# MCU.net
KiCad netlist of a schematic drawn in Altium Designer
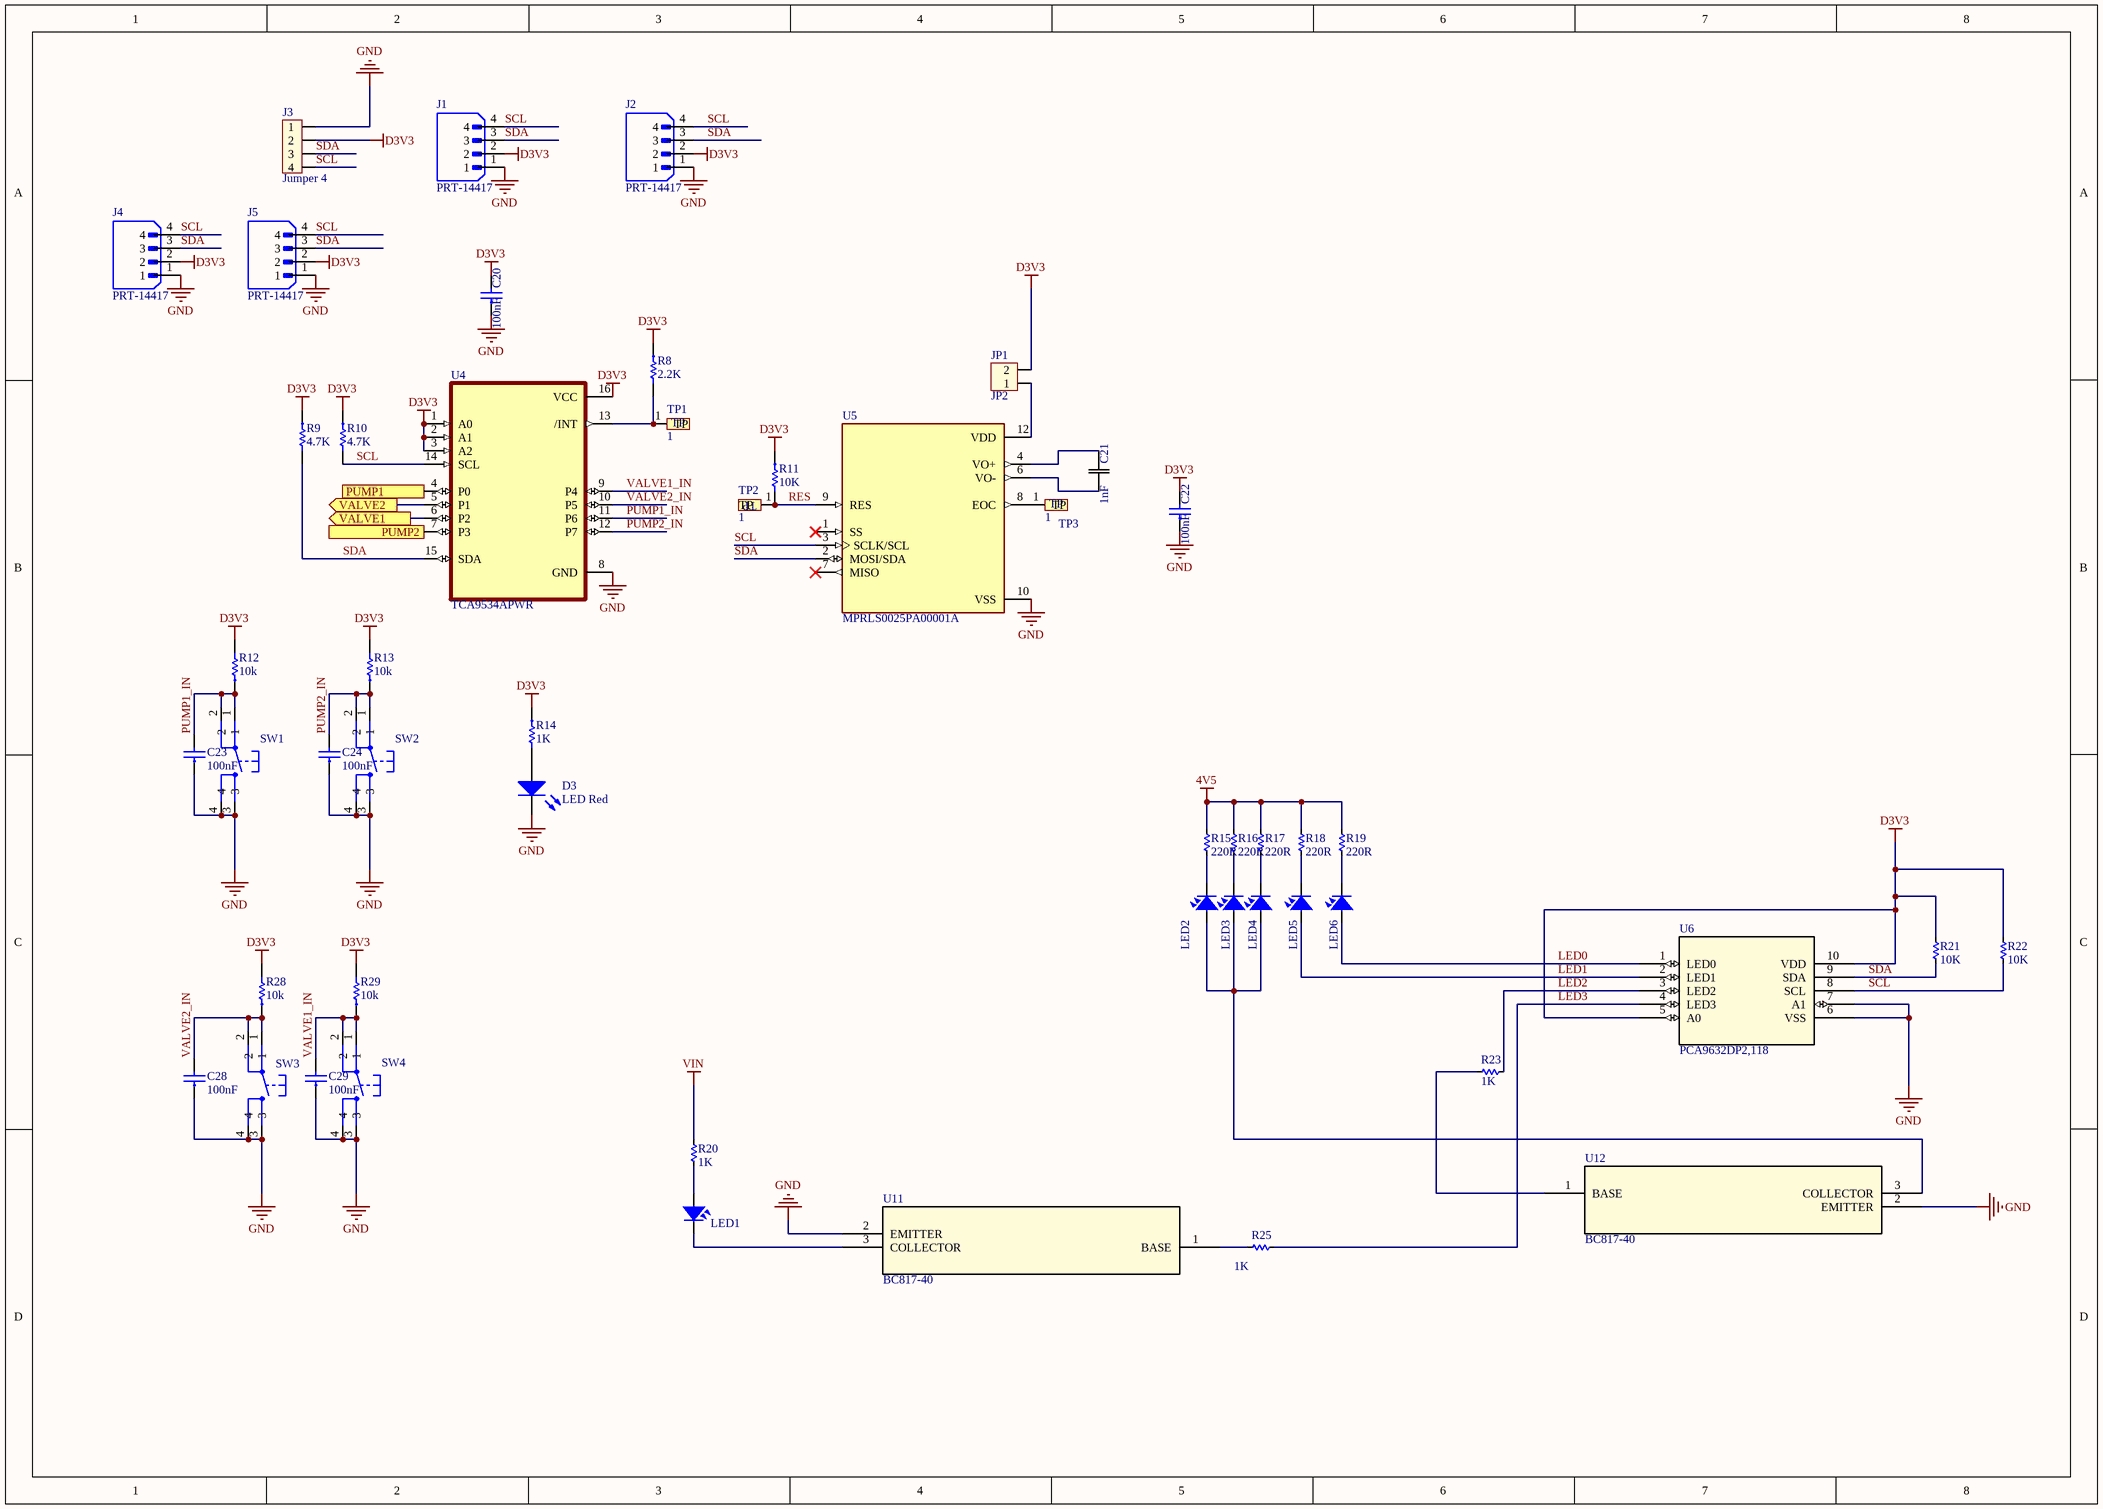
[diagram p0: MCU.SchDoc]

(export (version "E")
  (design (tool "Eeschema 10.0.6"))
  (components
    (comp (ref "C20")
      (value "100nF")
      (footprint "CN-SMD-0603")
      (description "CAP CER 100nF 10% 50V X7R 0603 SMD")
      (libsource (lib "2502-GMQLITE-MAIN") (part "CAPCER0001 100nF 10% 50V X7R 0603 SMD"))
    )
    (comp (ref "C21")
      (value "1nF")
      (footprint "CN-SMD-0603")
      (description "No Description Available")
      (fields
        (field (name "MANUFACTURER_PART_NUMBER") "GCJ188R71H102KA01D")
        (field (name "COPYRIGHT") "Copyright (C) 2026 Ultra Librarian. All rights reserved.")
      )
      (libsource (lib "GCJ188R71H102KA01D") (part "GCJ188R71H102KA01D"))
    )
    (comp (ref "C22")
      (value "100nF")
      (footprint "CL10A106MQ8NNNC:CAP_CL10_SAM-L")
      (description "CAP CER 100nF 10% 50V X7R 0603 SMD")
      (libsource (lib "2502-GMQLITE-MAIN") (part "CAPCER0001 100nF 10% 50V X7R 0603 SMD"))
    )
    (comp (ref "C23")
      (value "100nF")
      (footprint "CN-SMD-0603")
      (description "CAP CER 100nF 10% 50V X7R 0603 SMD")
      (libsource (lib "2502-GMQLITE-MAIN") (part "CAPCER0001 100nF 10% 50V X7R 0603 SMD"))
    )
    (comp (ref "C24")
      (value "100nF")
      (footprint "CN-SMD-0603")
      (description "CAP CER 100nF 10% 50V X7R 0603 SMD")
      (libsource (lib "2502-GMQLITE-MAIN") (part "CAPCER0001 100nF 10% 50V X7R 0603 SMD"))
    )
    (comp (ref "C28")
      (value "100nF")
      (footprint "CN-SMD-0603")
      (description "CAP CER 100nF 10% 50V X7R 0603 SMD")
      (libsource (lib "2502-GMQLITE-MAIN") (part "CAPCER0001 100nF 10% 50V X7R 0603 SMD"))
    )
    (comp (ref "C29")
      (value "100nF")
      (footprint "CN-SMD-0603")
      (description "CAP CER 100nF 10% 50V X7R 0603 SMD")
      (libsource (lib "2502-GMQLITE-MAIN") (part "CAPCER0001 100nF 10% 50V X7R 0603 SMD"))
    )
    (comp (ref "D3")
      (value "LED Red")
      (footprint "LED-0805-Red")
      (description "Lite-On LED Red 0603")
      (libsource (lib "diode") (part "LTST-C190KRKT"))
    )
    (comp (ref "J1")
      (value "PRT-14417")
      (footprint "SPARKFUN_PRT-14417")
      (description "QWIIC JST CONNECTOR - SMD 4-PIN")
      (fields (field (name "MF") "SparkFun Electronics"))
      (libsource (lib "PRT-14417") (part "PRT-14417"))
    )
    (comp (ref "J2")
      (value "PRT-14417")
      (footprint "SPARKFUN_PRT-14417")
      (description "QWIIC JST CONNECTOR - SMD 4-PIN")
      (fields (field (name "MF") "SparkFun Electronics"))
      (libsource (lib "PRT-14417") (part "PRT-14417"))
    )
    (comp (ref "J3")
      (value "Jumper 4")
      (footprint "JP4")
      (description "Jumper 3")
      (libsource (lib "hanguyen") (part "JP4"))
    )
    (comp (ref "J4")
      (value "PRT-14417")
      (footprint "SPARKFUN_PRT-14417")
      (description "QWIIC JST CONNECTOR - SMD 4-PIN")
      (fields (field (name "MF") "SparkFun Electronics"))
      (libsource (lib "PRT-14417") (part "PRT-14417"))
    )
    (comp (ref "J5")
      (value "PRT-14417")
      (footprint "SPARKFUN_PRT-14417")
      (description "QWIIC JST CONNECTOR - SMD 4-PIN")
      (fields (field (name "MF") "SparkFun Electronics"))
      (libsource (lib "PRT-14417") (part "PRT-14417"))
    )
    (comp (ref "JP1")
      (value "JP2")
      (footprint "JP2-CLOSED")
      (description "jumper 2.0 B")
      (libsource (lib "hanguyen") (part "Con2"))
    )
    (comp (ref "LED1")
      (value "LED")
      (footprint "LED-1206-Red")
      (description "LED Single colour Green and Red")
      (libsource (lib "Copy of KhanhBK_SCH_Library_1") (part "LED"))
    )
    (comp (ref "LED2")
      (value "LED")
      (footprint "LED-1206-Red")
      (description "LED Single colour Green and Red")
      (libsource (lib "Copy of KhanhBK_SCH_Library_1") (part "LED"))
    )
    (comp (ref "LED3")
      (value "LED")
      (footprint "LED-1206-Red")
      (description "LED Single colour Green and Red")
      (libsource (lib "Copy of KhanhBK_SCH_Library_1") (part "LED"))
    )
    (comp (ref "LED4")
      (value "LED")
      (footprint "LED-1206-Red")
      (description "LED Single colour Green and Red")
      (libsource (lib "Copy of KhanhBK_SCH_Library_1") (part "LED"))
    )
    (comp (ref "LED5")
      (value "LED")
      (footprint "LED-1206-Red")
      (description "LED Single colour Green and Red")
      (libsource (lib "Copy of KhanhBK_SCH_Library_1") (part "LED"))
    )
    (comp (ref "LED6")
      (value "LED")
      (footprint "LED-1206-Red")
      (description "LED Single colour Green and Red")
      (libsource (lib "Copy of KhanhBK_SCH_Library_1") (part "LED"))
    )
    (comp (ref "R8")
      (value "2.2K")
      (footprint "RES-SMD-0603")
      (description "RES CHP 8K4 1% 1/10W 0603 SMD")
      (libsource (lib "2502-GMQLITE-MAIN") (part "RESCHP0428 8K4 1% 0603 SMD"))
    )
    (comp (ref "R9")
      (value "4.7K")
      (footprint "RES-SMD-0603")
      (description "RES CHP 8K4 1% 1/10W 0603 SMD")
      (libsource (lib "2502-GMQLITE-MAIN") (part "RESCHP0428 8K4 1% 0603 SMD"))
    )
    (comp (ref "R10")
      (value "4.7K")
      (footprint "RES-SMD-0603")
      (description "RES CHP 8K4 1% 1/10W 0603 SMD")
      (libsource (lib "2502-GMQLITE-MAIN") (part "RESCHP0428 8K4 1% 0603 SMD"))
    )
    (comp (ref "R11")
      (value "10K")
      (footprint "RES-SMD-0603")
      (description "RES CHP 8K4 1% 1/10W 0603 SMD")
      (libsource (lib "2502-GMQLITE-MAIN") (part "RESCHP0428 8K4 1% 0603 SMD"))
    )
    (comp (ref "R12")
      (value "10k")
      (footprint "RES-SMD-0603")
      (description "RES CHP 8K4 1% 1/10W 0603 SMD")
      (libsource (lib "2502-GMQLITE-MAIN") (part "RESCHP0428 8K4 1% 0603 SMD"))
    )
    (comp (ref "R13")
      (value "10k")
      (footprint "RES-SMD-0603")
      (description "RES CHP 8K4 1% 1/10W 0603 SMD")
      (libsource (lib "2502-GMQLITE-MAIN") (part "RESCHP0428 8K4 1% 0603 SMD"))
    )
    (comp (ref "R14")
      (value "1K")
      (footprint "RES-SMD-0603")
      (description "RES CHP 8K4 1% 1/10W 0603 SMD")
      (libsource (lib "2502-GMQLITE-MAIN") (part "RESCHP0428 8K4 1% 0603 SMD"))
    )
    (comp (ref "R15")
      (value "220R")
      (footprint "RES-SMD-0603")
      (description "Resistor")
      (fields
        (field (name "MANUFACTURER") "Generic Components")
        (field (name "PUBLISHER") "Altium Hobart Technology Centre")
      )
      (libsource (lib "Copy of KhanhBK_SCH_Library_1") (part "Res-SMD"))
    )
    (comp (ref "R16")
      (value "220R")
      (footprint "RES-SMD-0603")
      (description "Resistor")
      (fields
        (field (name "MANUFACTURER") "Generic Components")
        (field (name "PUBLISHER") "Altium Hobart Technology Centre")
      )
      (libsource (lib "Copy of KhanhBK_SCH_Library_1") (part "Res-SMD"))
    )
    (comp (ref "R17")
      (value "220R")
      (footprint "RES-SMD-0603")
      (description "Resistor")
      (fields
        (field (name "MANUFACTURER") "Generic Components")
        (field (name "PUBLISHER") "Altium Hobart Technology Centre")
      )
      (libsource (lib "Copy of KhanhBK_SCH_Library_1") (part "Res-SMD"))
    )
    (comp (ref "R18")
      (value "220R")
      (footprint "RES-SMD-0603")
      (description "Resistor")
      (fields
        (field (name "MANUFACTURER") "Generic Components")
        (field (name "PUBLISHER") "Altium Hobart Technology Centre")
      )
      (libsource (lib "Copy of KhanhBK_SCH_Library_1") (part "Res-SMD"))
    )
    (comp (ref "R19")
      (value "220R")
      (footprint "RES-SMD-0603")
      (description "Resistor")
      (fields
        (field (name "MANUFACTURER") "Generic Components")
        (field (name "PUBLISHER") "Altium Hobart Technology Centre")
      )
      (libsource (lib "Copy of KhanhBK_SCH_Library_1") (part "Res-SMD"))
    )
    (comp (ref "R20")
      (value "1K")
      (footprint "RES-SMD-0603")
      (description "Resistor")
      (fields
        (field (name "MANUFACTURER") "Generic Components")
        (field (name "PUBLISHER") "Altium Hobart Technology Centre")
      )
      (libsource (lib "Copy of KhanhBK_SCH_Library_1") (part "Res-SMD"))
    )
    (comp (ref "R21")
      (value "10K")
      (footprint "RES-SMD-0603")
      (description "Resistor")
      (fields
        (field (name "MANUFACTURER") "Generic Components")
        (field (name "PUBLISHER") "Altium Hobart Technology Centre")
      )
      (libsource (lib "Copy of KhanhBK_SCH_Library_1") (part "Res-SMD"))
    )
    (comp (ref "R22")
      (value "10K")
      (footprint "RES-SMD-0603")
      (description "Resistor")
      (fields
        (field (name "MANUFACTURER") "Generic Components")
        (field (name "PUBLISHER") "Altium Hobart Technology Centre")
      )
      (libsource (lib "Copy of KhanhBK_SCH_Library_1") (part "Res-SMD"))
    )
    (comp (ref "R23")
      (value "1K")
      (footprint "RES-SMD-0603")
      (description "Resistor")
      (fields
        (field (name "MANUFACTURER") "Generic Components")
        (field (name "PUBLISHER") "Altium Hobart Technology Centre")
      )
      (libsource (lib "Copy of KhanhBK_SCH_Library_1") (part "Res-SMD"))
    )
    (comp (ref "R25")
      (value "1K")
      (footprint "RES-SMD-0603")
      (description "Resistor")
      (fields
        (field (name "MANUFACTURER") "Generic Components")
        (field (name "PUBLISHER") "Altium Hobart Technology Centre")
      )
      (libsource (lib "Copy of KhanhBK_SCH_Library_1") (part "Res-SMD"))
    )
    (comp (ref "R28")
      (value "10k")
      (footprint "RES-SMD-0603")
      (description "RES CHP 8K4 1% 1/10W 0603 SMD")
      (libsource (lib "2502-GMQLITE-MAIN") (part "RESCHP0428 8K4 1% 0603 SMD"))
    )
    (comp (ref "R29")
      (value "10k")
      (footprint "RES-SMD-0603")
      (description "RES CHP 8K4 1% 1/10W 0603 SMD")
      (libsource (lib "2502-GMQLITE-MAIN") (part "RESCHP0428 8K4 1% 0603 SMD"))
    )
    (comp (ref "SW1")
      (value "SW2")
      (footprint "SW2-DIP")
      (description "Switch button 4 pin")
      (libsource (lib "Stm32_Flyback_Driver_250814_1") (part "SW2"))
    )
    (comp (ref "SW2")
      (value "SW2")
      (footprint "SW2-DIP")
      (description "Switch button 4 pin")
      (libsource (lib "Stm32_Flyback_Driver_250814_1") (part "SW2"))
    )
    (comp (ref "SW3")
      (value "SW2")
      (footprint "SW2-DIP")
      (description "Switch button 4 pin")
      (libsource (lib "Stm32_Flyback_Driver_250814_1") (part "SW2"))
    )
    (comp (ref "SW4")
      (value "SW2")
      (footprint "SW2-DIP")
      (description "Switch button 4 pin")
      (libsource (lib "Stm32_Flyback_Driver_250814_1") (part "SW2"))
    )
    (comp (ref "TP1")
      (value "1")
      (footprint "TP - 2")
      (description "CONNECT 1")
      (libsource (lib "hanguyen") (part "TP"))
    )
    (comp (ref "TP2")
      (value "1")
      (footprint "TP - 2")
      (description "CONNECT 1")
      (libsource (lib "") (part "TP_1"))
    )
    (comp (ref "TP3")
      (value "1")
      (footprint "TP - 2")
      (description "CONNECT 1")
      (libsource (lib "hanguyen") (part "TP"))
    )
    (comp (ref "U4")
      (value "TCA9534APWR")
      (footprint "SOP65P640X120-16N")
      (description "8-bit 1.65- to 5.5-V I2C/SMBus I/O expander with interrupt, & config registers")
      (fields (field (name "MF") "Texas Instruments"))
      (libsource (lib "TCA9534APWR") (part "TCA9534APWR"))
    )
    (comp (ref "U5")
      (value "MPRLS0025PA00001A")
      (footprint "SnapEDApcb:XDCR_MPRLS0025PA00001A")
      (description "Pressure Sensor 25PSI _172.37kPa_ Absolute Male - 0.1 _2.5mm_ Tube 24 b 12-SMD Module")
      (fields (field (name "DIGI-KEY_PART_NUMBER") "480-7098-1-ND") (field (name "MF") "Honeywell Sensing"))
      (libsource (lib "SnapEDAsch") (part "MPRLS0025PA00001A"))
    )
    (comp (ref "U6")
      (value "PCA9632DP2,118")
      (footprint "TSSOP10_3P1X3P1_NXP")
      (description "No Description Available")
      (fields (field (name "COPYRIGHT") "Copyright (C) 2026 Ultra Librarian. All rights reserved."))
      (libsource (lib "PCA9632DP2,118") (part "PCA9632DP2,118"))
    )
    (comp (ref "U11")
      (value "BC817-40")
      (footprint "SOT23_NEX")
      (description "No Description Available")
      (fields (field (name "COPYRIGHT") "Copyright (C) 2026 Ultra Librarian. All rights reserved."))
      (libsource (lib "") (part "BC817-40_1"))
    )
    (comp (ref "U12")
      (value "BC817-40")
      (footprint "SOT23_NEX")
      (description "No Description Available")
      (fields (field (name "COPYRIGHT") "Copyright (C) 2026 Ultra Librarian. All rights reserved."))
      (libsource (lib "BC817-40") (part "BC817-40"))
    )
  )
  (nets
    (net (code "1") (name "/LED0") (class "Default")
      (node (ref "LED6") (pin "1") (pinfunction "1_1") (pintype "passive"))
      (node (ref "U6") (pin "1") (pinfunction "LED0_1") (pintype "bidirectional"))
    )
    (net (code "2") (name "/LED1") (class "Default")
      (node (ref "LED5") (pin "1") (pinfunction "1_1") (pintype "passive"))
      (node (ref "U6") (pin "2") (pinfunction "LED1_2") (pintype "bidirectional"))
    )
    (net (code "3") (name "/LED2") (class "Default")
      (node (ref "R23") (pin "2") (pinfunction "2_2") (pintype "passive"))
      (node (ref "U6") (pin "3") (pinfunction "LED2_3") (pintype "bidirectional"))
    )
    (net (code "4") (name "/LED3") (class "Default")
      (node (ref "R25") (pin "1") (pinfunction "1_1") (pintype "passive"))
      (node (ref "U6") (pin "4") (pinfunction "LED3_4") (pintype "bidirectional"))
    )
    (net (code "5") (name "/PUMP1") (class "Default")
      (node (ref "U4") (pin "4") (pinfunction "P0_4") (pintype "bidirectional"))
    )
    (net (code "6") (name "/PUMP1_IN") (class "Default")
      (node (ref "C23") (pin "2") (pinfunction "2_2") (pintype "passive"))
      (node (ref "R12") (pin "1") (pinfunction "1_1") (pintype "passive"))
      (node (ref "SW1") (pin "1") (pinfunction "1_1") (pintype "passive"))
      (node (ref "SW1") (pin "2") (pinfunction "2_2") (pintype "passive"))
      (node (ref "U4") (pin "11") (pinfunction "P6_11") (pintype "bidirectional"))
    )
    (net (code "7") (name "/PUMP2") (class "Default")
      (node (ref "U4") (pin "7") (pinfunction "P3_7") (pintype "bidirectional"))
    )
    (net (code "8") (name "/PUMP2_IN") (class "Default")
      (node (ref "C24") (pin "2") (pinfunction "2_2") (pintype "passive"))
      (node (ref "R13") (pin "1") (pinfunction "1_1") (pintype "passive"))
      (node (ref "SW2") (pin "1") (pinfunction "1_1") (pintype "passive"))
      (node (ref "SW2") (pin "2") (pinfunction "2_2") (pintype "passive"))
      (node (ref "U4") (pin "12") (pinfunction "P7_12") (pintype "bidirectional"))
    )
    (net (code "9") (name "/RES") (class "Default")
      (node (ref "R11") (pin "2") (pinfunction "2_2") (pintype "passive"))
      (node (ref "TP2") (pin "1") (pinfunction "TP_1") (pintype "passive"))
      (node (ref "U5") (pin "9") (pinfunction "RES_9") (pintype "input"))
    )
    (net (code "10") (name "/SCL") (class "Default")
      (node (ref "J1") (pin "4") (pinfunction "4_4") (pintype "passive"))
      (node (ref "J2") (pin "4") (pinfunction "4_4") (pintype "passive"))
      (node (ref "J3") (pin "4") (pinfunction "4_4") (pintype "passive"))
      (node (ref "J4") (pin "4") (pinfunction "4_4") (pintype "passive"))
      (node (ref "J5") (pin "4") (pinfunction "4_4") (pintype "passive"))
      (node (ref "R10") (pin "2") (pinfunction "2_2") (pintype "passive"))
      (node (ref "R22") (pin "2") (pinfunction "2_2") (pintype "passive"))
      (node (ref "U4") (pin "14") (pinfunction "SCL_14") (pintype "input"))
      (node (ref "U5") (pin "3") (pinfunction "SCLK/SCL_3") (pintype "input"))
      (node (ref "U6") (pin "8") (pinfunction "SCL_8") (pintype "passive"))
    )
    (net (code "11") (name "/SDA") (class "Default")
      (node (ref "J1") (pin "3") (pinfunction "3_3") (pintype "passive"))
      (node (ref "J2") (pin "3") (pinfunction "3_3") (pintype "passive"))
      (node (ref "J3") (pin "3") (pinfunction "3_3") (pintype "passive"))
      (node (ref "J4") (pin "3") (pinfunction "3_3") (pintype "passive"))
      (node (ref "J5") (pin "3") (pinfunction "3_3") (pintype "passive"))
      (node (ref "R21") (pin "2") (pinfunction "2_2") (pintype "passive"))
      (node (ref "R9") (pin "2") (pinfunction "2_2") (pintype "passive"))
      (node (ref "U4") (pin "15") (pinfunction "SDA_15") (pintype "bidirectional"))
      (node (ref "U5") (pin "2") (pinfunction "MOSI/SDA_2") (pintype "bidirectional"))
      (node (ref "U6") (pin "9") (pinfunction "SDA_9") (pintype "passive"))
    )
    (net (code "12") (name "/VALVE1") (class "Default")
      (node (ref "U4") (pin "6") (pinfunction "P2_6") (pintype "bidirectional"))
    )
    (net (code "13") (name "/VALVE1_IN") (class "Default")
      (node (ref "C29") (pin "2") (pinfunction "2_2") (pintype "passive"))
      (node (ref "R29") (pin "1") (pinfunction "1_1") (pintype "passive"))
      (node (ref "SW4") (pin "1") (pinfunction "1_1") (pintype "passive"))
      (node (ref "SW4") (pin "2") (pinfunction "2_2") (pintype "passive"))
      (node (ref "U4") (pin "9") (pinfunction "P4_9") (pintype "bidirectional"))
    )
    (net (code "14") (name "/VALVE2") (class "Default")
      (node (ref "U4") (pin "5") (pinfunction "P1_5") (pintype "bidirectional"))
    )
    (net (code "15") (name "/VALVE2_IN") (class "Default")
      (node (ref "C28") (pin "2") (pinfunction "2_2") (pintype "passive"))
      (node (ref "R28") (pin "1") (pinfunction "1_1") (pintype "passive"))
      (node (ref "SW3") (pin "1") (pinfunction "1_1") (pintype "passive"))
      (node (ref "SW3") (pin "2") (pinfunction "2_2") (pintype "passive"))
      (node (ref "U4") (pin "10") (pinfunction "P5_10") (pintype "bidirectional"))
    )
    (net (code "16") (name "4V5") (class "Default")
      (node (ref "R15") (pin "1") (pinfunction "1_1") (pintype "passive"))
      (node (ref "R16") (pin "1") (pinfunction "1_1") (pintype "passive"))
      (node (ref "R17") (pin "1") (pinfunction "1_1") (pintype "passive"))
      (node (ref "R18") (pin "1") (pinfunction "1_1") (pintype "passive"))
      (node (ref "R19") (pin "1") (pinfunction "1_1") (pintype "passive"))
    )
    (net (code "17") (name "D3V3") (class "Default")
      (node (ref "C20") (pin "2") (pinfunction "2_2") (pintype "passive"))
      (node (ref "C22") (pin "2") (pinfunction "2_2") (pintype "passive"))
      (node (ref "J1") (pin "2") (pinfunction "2_2") (pintype "passive"))
      (node (ref "J2") (pin "2") (pinfunction "2_2") (pintype "passive"))
      (node (ref "J3") (pin "2") (pinfunction "2_2") (pintype "passive"))
      (node (ref "J4") (pin "2") (pinfunction "2_2") (pintype "passive"))
      (node (ref "J5") (pin "2") (pinfunction "2_2") (pintype "passive"))
      (node (ref "JP1") (pin "2") (pinfunction "2_2") (pintype "passive"))
      (node (ref "R10") (pin "1") (pinfunction "1_1") (pintype "passive"))
      (node (ref "R11") (pin "1") (pinfunction "1_1") (pintype "passive"))
      (node (ref "R12") (pin "2") (pinfunction "2_2") (pintype "passive"))
      (node (ref "R13") (pin "2") (pinfunction "2_2") (pintype "passive"))
      (node (ref "R14") (pin "1") (pinfunction "1_1") (pintype "passive"))
      (node (ref "R21") (pin "1") (pinfunction "1_1") (pintype "passive"))
      (node (ref "R22") (pin "1") (pinfunction "1_1") (pintype "passive"))
      (node (ref "R28") (pin "2") (pinfunction "2_2") (pintype "passive"))
      (node (ref "R29") (pin "2") (pinfunction "2_2") (pintype "passive"))
      (node (ref "R8") (pin "1") (pinfunction "1_1") (pintype "passive"))
      (node (ref "R9") (pin "1") (pinfunction "1_1") (pintype "passive"))
      (node (ref "U4") (pin "1") (pinfunction "A0_1") (pintype "input"))
      (node (ref "U4") (pin "16") (pinfunction "VCC_16") (pintype "power_in"))
      (node (ref "U4") (pin "2") (pinfunction "A1_2") (pintype "input"))
      (node (ref "U4") (pin "3") (pinfunction "A2_3") (pintype "input"))
      (node (ref "U6") (pin "10") (pinfunction "VDD_10") (pintype "power_in"))
      (node (ref "U6") (pin "5") (pinfunction "A0_5") (pintype "bidirectional"))
    )
    (net (code "18") (name "GND") (class "Default")
      (node (ref "C20") (pin "1") (pinfunction "1_1") (pintype "passive"))
      (node (ref "C22") (pin "1") (pinfunction "1_1") (pintype "passive"))
      (node (ref "C23") (pin "1") (pinfunction "1_1") (pintype "passive"))
      (node (ref "C24") (pin "1") (pinfunction "1_1") (pintype "passive"))
      (node (ref "C28") (pin "1") (pinfunction "1_1") (pintype "passive"))
      (node (ref "C29") (pin "1") (pinfunction "1_1") (pintype "passive"))
      (node (ref "D3") (pin "2") (pinfunction "K_2") (pintype "passive"))
      (node (ref "J1") (pin "1") (pinfunction "1_1") (pintype "passive"))
      (node (ref "J2") (pin "1") (pinfunction "1_1") (pintype "passive"))
      (node (ref "J3") (pin "1") (pinfunction "1_1") (pintype "passive"))
      (node (ref "J4") (pin "1") (pinfunction "1_1") (pintype "passive"))
      (node (ref "J5") (pin "1") (pinfunction "1_1") (pintype "passive"))
      (node (ref "SW1") (pin "3") (pinfunction "3_3") (pintype "passive"))
      (node (ref "SW1") (pin "4") (pinfunction "4_4") (pintype "passive"))
      (node (ref "SW2") (pin "3") (pinfunction "3_3") (pintype "passive"))
      (node (ref "SW2") (pin "4") (pinfunction "4_4") (pintype "passive"))
      (node (ref "SW3") (pin "3") (pinfunction "3_3") (pintype "passive"))
      (node (ref "SW3") (pin "4") (pinfunction "4_4") (pintype "passive"))
      (node (ref "SW4") (pin "3") (pinfunction "3_3") (pintype "passive"))
      (node (ref "SW4") (pin "4") (pinfunction "4_4") (pintype "passive"))
      (node (ref "U11") (pin "2") (pinfunction "EMITTER_2") (pintype "passive"))
      (node (ref "U12") (pin "2") (pinfunction "EMITTER_2") (pintype "passive"))
      (node (ref "U4") (pin "8") (pinfunction "GND_8") (pintype "power_in"))
      (node (ref "U5") (pin "10") (pinfunction "VSS_10") (pintype "power_in"))
      (node (ref "U6") (pin "6") (pinfunction "VSS_6") (pintype "power_in"))
      (node (ref "U6") (pin "7") (pinfunction "A1_7") (pintype "bidirectional"))
    )
    (net (code "19") (name "Net-(D3-A)") (class "Default")
      (node (ref "D3") (pin "1") (pinfunction "A_1") (pintype "passive"))
      (node (ref "R14") (pin "2") (pinfunction "2_2") (pintype "passive"))
    )
    (net (code "20") (name "Net-(LED1-Pad1)") (class "Default")
      (node (ref "LED1") (pin "1") (pinfunction "1_1") (pintype "passive"))
      (node (ref "R20") (pin "2") (pinfunction "2_2") (pintype "passive"))
    )
    (net (code "21") (name "Net-(LED2-Pad2)") (class "Default")
      (node (ref "LED2") (pin "2") (pinfunction "2_2") (pintype "passive"))
      (node (ref "R15") (pin "2") (pinfunction "2_2") (pintype "passive"))
    )
    (net (code "22") (name "Net-(LED3-Pad2)") (class "Default")
      (node (ref "LED3") (pin "2") (pinfunction "2_2") (pintype "passive"))
      (node (ref "R16") (pin "2") (pinfunction "2_2") (pintype "passive"))
    )
    (net (code "23") (name "Net-(LED4-Pad2)") (class "Default")
      (node (ref "LED4") (pin "2") (pinfunction "2_2") (pintype "passive"))
      (node (ref "R17") (pin "2") (pinfunction "2_2") (pintype "passive"))
    )
    (net (code "24") (name "Net-(LED5-Pad2)") (class "Default")
      (node (ref "LED5") (pin "2") (pinfunction "2_2") (pintype "passive"))
      (node (ref "R18") (pin "2") (pinfunction "2_2") (pintype "passive"))
    )
    (net (code "25") (name "Net-(LED6-Pad2)") (class "Default")
      (node (ref "LED6") (pin "2") (pinfunction "2_2") (pintype "passive"))
      (node (ref "R19") (pin "2") (pinfunction "2_2") (pintype "passive"))
    )
    (net (code "26") (name "Net-(TP1-TP)") (class "Default")
      (node (ref "R8") (pin "2") (pinfunction "2_2") (pintype "passive"))
      (node (ref "TP1") (pin "1") (pinfunction "TP_1") (pintype "passive"))
      (node (ref "U4") (pin "13") (pinfunction "/INT_13") (pintype "output"))
    )
    (net (code "27") (name "Net-(TP3-TP)") (class "Default")
      (node (ref "TP3") (pin "1") (pinfunction "TP_1") (pintype "passive"))
      (node (ref "U5") (pin "8") (pinfunction "EOC_8") (pintype "output"))
    )
    (net (code "28") (name "Net-(U5-VDD)") (class "Default")
      (node (ref "JP1") (pin "1") (pinfunction "1_1") (pintype "passive"))
      (node (ref "U5") (pin "12") (pinfunction "VDD_12") (pintype "power_in"))
    )
    (net (code "29") (name "Net-(U5-VO+)") (class "Default")
      (node (ref "C21") (pin "2") (pinfunction "2_2") (pintype "passive"))
      (node (ref "U5") (pin "4") (pinfunction "VO+_4") (pintype "output"))
    )
    (net (code "30") (name "Net-(U5-VO-)") (class "Default")
      (node (ref "C21") (pin "1") (pinfunction "1_1") (pintype "passive"))
      (node (ref "U5") (pin "6") (pinfunction "VO-_6") (pintype "output"))
    )
    (net (code "31") (name "Net-(U11-BASE)") (class "Default")
      (node (ref "R25") (pin "2") (pinfunction "2_2") (pintype "passive"))
      (node (ref "U11") (pin "1") (pinfunction "BASE_1") (pintype "passive"))
    )
    (net (code "32") (name "Net-(U11-COLLECTOR)") (class "Default")
      (node (ref "LED1") (pin "2") (pinfunction "2_2") (pintype "passive"))
      (node (ref "U11") (pin "3") (pinfunction "COLLECTOR_3") (pintype "passive"))
    )
    (net (code "33") (name "Net-(U12-BASE)") (class "Default")
      (node (ref "R23") (pin "1") (pinfunction "1_1") (pintype "passive"))
      (node (ref "U12") (pin "1") (pinfunction "BASE_1") (pintype "passive"))
    )
    (net (code "34") (name "Net-(U12-COLLECTOR)") (class "Default")
      (node (ref "LED2") (pin "1") (pinfunction "1_1") (pintype "passive"))
      (node (ref "LED3") (pin "1") (pinfunction "1_1") (pintype "passive"))
      (node (ref "LED4") (pin "1") (pinfunction "1_1") (pintype "passive"))
      (node (ref "U12") (pin "3") (pinfunction "COLLECTOR_3") (pintype "passive"))
    )
    (net (code "35") (name "VIN") (class "Default")
      (node (ref "R20") (pin "1") (pinfunction "1_1") (pintype "passive"))
    )
    (net (code "36") (name "unconnected-(U5-MISO-Pad7)") (class "Default")
      (node (ref "U5") (pin "7") (pinfunction "MISO_7") (pintype "output+no_connect"))
    )
    (net (code "37") (name "unconnected-(U5-SS-Pad1)") (class "Default")
      (node (ref "U5") (pin "1") (pinfunction "SS_1") (pintype "input+no_connect"))
    )
  )
)
